# LED_Driver.net
KiCad netlist of a schematic drawn in Altium Designer
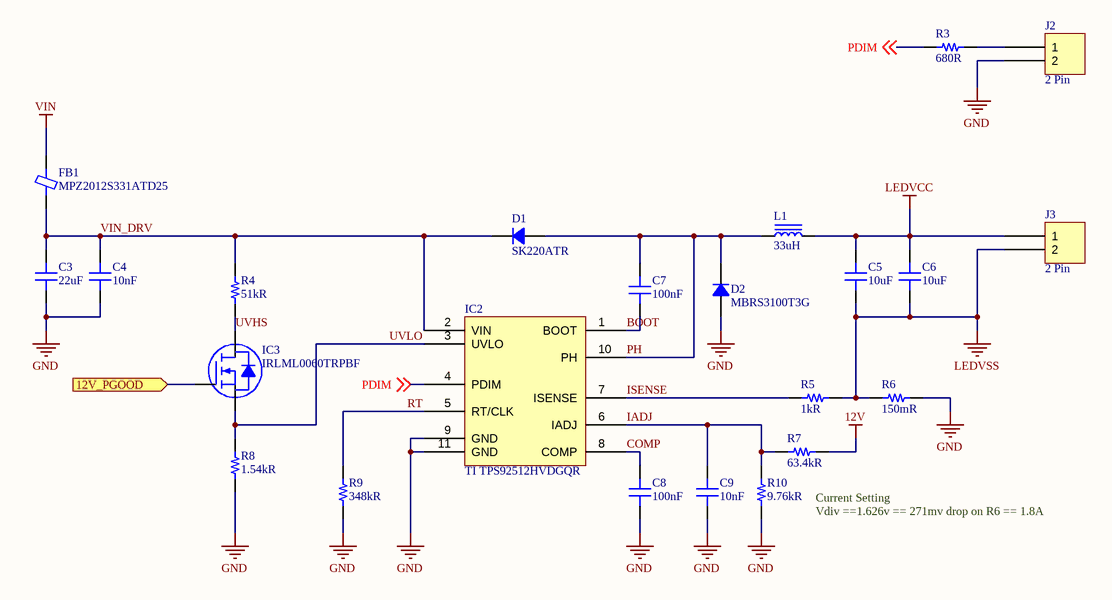
[diagram p0: LED Driver.SchDoc]

(export (version "E")
  (design (tool "Eeschema 10.0.6"))
  (components
    (comp (ref "C3")
      (value "22uF")
      (footprint "TDK CKG57N")
      (description "TDK - CKG57NX7S2A226M500JH - CAP, 22µF, 100V, 20%, X7S, 2220")
      (fields (field (name "TOLERANCE") "20%") (field (name "VOLTAGE") "100V"))
      (libsource (lib "SCH - PASSIVES - CAPACITOR") (part "Capacitor"))
    )
    (comp (ref "C4")
      (value "10nF")
      (footprint "CAP 0603/1608")
      (description "Multilayer Ceramic Capacitors MLCC - SMD/SMT .01uF 100Volts 10%")
      (fields (field (name "TOLERANCE") "10%") (field (name "VOLTAGE") "100V"))
      (libsource (lib "SCH - PASSIVES - CAPACITOR") (part "Capacitor"))
    )
    (comp (ref "C5")
      (value "10uF")
      (footprint "CAP 1210/3225 - 2.8MM")
      (description "CAP CER 10UF 50V X7R 1210")
      (fields (field (name "TOLERANCE") "10%"))
      (libsource (lib "SCH - PASSIVES - CAPACITOR") (part "Capacitor"))
    )
    (comp (ref "C6")
      (value "10uF")
      (footprint "CAP 1210/3225 - 2.8MM")
      (description "CAP CER 10UF 50V X7R 1210")
      (fields (field (name "TOLERANCE") "10%"))
      (libsource (lib "SCH - PASSIVES - CAPACITOR") (part "Capacitor"))
    )
    (comp (ref "C7")
      (value "100nF")
      (footprint "CAP 0805/2012")
      (description "Multilayer Ceramic Capacitors MLCC - SMD/SMT 50volts 0.1uF X7R 20%")
      (fields (field (name "TOLERANCE") "20%"))
      (libsource (lib "SCH - PASSIVES - CAPACITOR") (part "Capacitor"))
    )
    (comp (ref "C8")
      (value "100nF")
      (footprint "CAP 0402/1005")
      (description "MURATA - GRM155R62A104KE14D - CAP, 0.1µF, 100V, 10%, X5R, 0402")
      (fields (field (name "TOLERANCE") "10%"))
      (libsource (lib "SCH - PASSIVES - CAPACITOR") (part "Capacitor"))
    )
    (comp (ref "C9")
      (value "10nF")
      (footprint "CAP 0402/1005")
      (description "TAIYO YUDEN - TMK105B7103KV-F - CERAMIC CAPACITOR 0.01UF, 25V, X7R, 10%, 0402, FULL REEL")
      (fields (field (name "TOLERANCE") "10%") (field (name "VOLTAGE") "25V"))
      (libsource (lib "SCH - PASSIVES - CAPACITOR") (part "Capacitor"))
    )
    (comp (ref "D1")
      (value "SK220ATR")
      (footprint "ST DO214AC SMA")
      (description "DIODE SCHOTTKY 200V 2A SMA")
      (libsource (lib "SCH - DIODES - DIODE") (part "Diode"))
    )
    (comp (ref "D2")
      (value "MBRS3100T3G")
      (footprint "ST DO214AB SMC")
      (description "DIODE SCHOTTKY 100V 3A SMC")
      (libsource (lib "SCH - DIODES - DIODE") (part "Diode"))
    )
    (comp (ref "FB1")
      (value "MPZ2012S331ATD25")
      (footprint "FER 0805/2012")
      (description "Ferrite Beads 0805 330ohms 2500mA Power Line AEC-Q200")
      (fields (field (name "TOLERANCE") "25%"))
      (libsource (lib "SCH - PASSIVES - FERRITE CHIP") (part "Ferrite Chip"))
    )
    (comp (ref "IC2")
      (value "TI TPS92512HVDGQR")
      (footprint "TI MSOP-10 DGQ")
      (description "IC LED CNV CONST CUR 2.5A 10MSOP")
      (libsource (lib "SCH - DRIVER - LED - TI TPS92512HVDGQR") (part "TI TPS92512HVDGQR"))
    )
    (comp (ref "IC3")
      (value "IRLML0060TRPBF")
      (footprint "INFINEON SOT-23-3")
      (description "MOSFET MOSFT 60V 2.7A 92mOhm 2.5nC Qg")
      (libsource (lib "SCH - FET - N-CH - INFINEON MOSFET N-CH SOT-23-3 GSD") (part "INFINEON MOSFET N-CH SOT-23-3 GSD"))
    )
    (comp (ref "J2")
      (value "2 Pin")
      (footprint "TE 282834-2")
      (description "TERM BLK 2P SIDE ENT 2.54MM PCB")
      (fields (field (name "VOLTAGE") "150V"))
      (libsource (lib "SCH - CONNECTORS - 2 PIN") (part "2 Pin"))
    )
    (comp (ref "J3")
      (value "2 Pin")
      (footprint "FCI 06-381-2PIN")
      (description "TERM BLOCK HDR 2POS 90DEG 3.81MM")
      (libsource (lib "SCH - CONNECTORS - 2 PIN") (part "2 Pin"))
    )
    (comp (ref "L1")
      (value "33uH")
      (footprint "TDK SLF12575")
      (description "INDUCTOR SHIELD PWR 33UH 12575")
      (fields (field (name "TOLERANCE") "20%"))
      (libsource (lib "SCH - PASSIVES - INDUCTOR") (part "Inductor"))
    )
    (comp (ref "R3")
      (value "680R")
      (footprint "RES 0402/1005")
      (description "ESR Series 680 Ω ±5 % 0.33 W ±200 ppm/°C 1206 SMT Anti-Surge Chip Resistor")
      (fields (field (name "TOLERANCE") "5%"))
      (libsource (lib "SCH - PASSIVES - RESISTOR") (part "Resistor"))
    )
    (comp (ref "R4")
      (value "51kR")
      (footprint "RES 0402/1005")
      (description "RES SMD 51K OHM 5% 1/16W 0402")
      (fields (field (name "TOLERANCE") "5%"))
      (libsource (lib "SCH - PASSIVES - RESISTOR") (part "Resistor"))
    )
    (comp (ref "R5")
      (value "1kR")
      (footprint "RES 0402/1005")
      (description "RES SMD 1K OHM 1% 1/16W 0402")
      (fields (field (name "TOLERANCE") "1%"))
      (libsource (lib "SCH - PASSIVES - RESISTOR") (part "Resistor"))
    )
    (comp (ref "R6")
      (value "150mR")
      (footprint "STACKPOLE CSRN2512")
      (description "RES 0.15 OHM 1% 2W 2512")
      (fields (field (name "TOLERANCE") "1%"))
      (libsource (lib "SCH - PASSIVES - RESISTOR") (part "Resistor"))
    )
    (comp (ref "R7")
      (value "63.4kR")
      (footprint "RES 0402/1005")
      (description "Thick Film Resistors - SMD 63.4K OHM 1%")
      (fields (field (name "TOLERANCE") "1%"))
      (libsource (lib "SCH - PASSIVES - RESISTOR") (part "Resistor"))
    )
    (comp (ref "R8")
      (value "1.54kR")
      (footprint "RES 0402/1005")
      (description "RES SMD 1.54K OHM 1% 1/16W 0402")
      (fields (field (name "TOLERANCE") "1%"))
      (libsource (lib "SCH - PASSIVES - RESISTOR") (part "Resistor"))
    )
    (comp (ref "R9")
      (value "348kR")
      (footprint "RES 0402/1005")
      (description "Res Thick Film 0402 348K Ohm 1% 1/16W ±100ppm/°C Molded SMD Paper T/R")
      (fields (field (name "TOLERANCE") "1%"))
      (libsource (lib "SCH - PASSIVES - RESISTOR") (part "Resistor"))
    )
    (comp (ref "R10")
      (value "9.76kR")
      (footprint "RES 0402/1005")
      (description "Thick Film Resistors - SMD 9.76K OHM 1%")
      (fields (field (name "TOLERANCE") "1%"))
      (libsource (lib "SCH - PASSIVES - RESISTOR") (part "Resistor"))
    )
  )
  (nets
    (net (code "1") (name "/12V_PGOOD") (class "Default")
      (node (ref "IC3") (pin "1") (pinfunction "G_1") (pintype "passive"))
    )
    (net (code "2") (name "/BOOT") (class "Default")
      (node (ref "C7") (pin "2") (pinfunction "2_2") (pintype "passive"))
      (node (ref "IC2") (pin "1") (pinfunction "BOOT_1") (pintype "passive"))
    )
    (net (code "3") (name "/COMP") (class "Default")
      (node (ref "C8") (pin "1") (pinfunction "1_1") (pintype "passive"))
      (node (ref "IC2") (pin "8") (pinfunction "COMP_8") (pintype "passive"))
    )
    (net (code "4") (name "/IADJ") (class "Default")
      (node (ref "C9") (pin "2") (pinfunction "2_2") (pintype "passive"))
      (node (ref "IC2") (pin "6") (pinfunction "IADJ_6") (pintype "passive"))
      (node (ref "R10") (pin "2") (pinfunction "2_2") (pintype "passive"))
      (node (ref "R7") (pin "2") (pinfunction "2_2") (pintype "passive"))
    )
    (net (code "5") (name "/ISENSE") (class "Default")
      (node (ref "IC2") (pin "7") (pinfunction "ISENSE_7") (pintype "passive"))
      (node (ref "R5") (pin "1") (pinfunction "1_1") (pintype "passive"))
    )
    (net (code "6") (name "/PH") (class "Default")
      (node (ref "C7") (pin "1") (pinfunction "1_1") (pintype "passive"))
      (node (ref "D1") (pin "1") (pinfunction "1_1") (pintype "passive"))
      (node (ref "D2") (pin "2") (pinfunction "2_2") (pintype "passive"))
      (node (ref "IC2") (pin "10") (pinfunction "PH_10") (pintype "passive"))
      (node (ref "L1") (pin "1") (pinfunction "1_1") (pintype "passive"))
    )
    (net (code "7") (name "/RT") (class "Default")
      (node (ref "IC2") (pin "5") (pinfunction "RT/CLK_5") (pintype "passive"))
      (node (ref "R9") (pin "2") (pinfunction "2_2") (pintype "passive"))
    )
    (net (code "8") (name "/UVHS") (class "Default")
      (node (ref "IC3") (pin "3") (pinfunction "D_3") (pintype "passive"))
      (node (ref "R4") (pin "1") (pinfunction "1_1") (pintype "passive"))
    )
    (net (code "9") (name "/UVLO") (class "Default")
      (node (ref "IC2") (pin "3") (pinfunction "UVLO_3") (pintype "passive"))
      (node (ref "IC3") (pin "2") (pinfunction "S_2") (pintype "passive"))
      (node (ref "R8") (pin "2") (pinfunction "2_2") (pintype "passive"))
    )
    (net (code "10") (name "/VIN_DRV") (class "Default")
      (node (ref "C3") (pin "2") (pinfunction "2_2") (pintype "passive"))
      (node (ref "C4") (pin "2") (pinfunction "2_2") (pintype "passive"))
      (node (ref "D1") (pin "2") (pinfunction "2_2") (pintype "passive"))
      (node (ref "FB1") (pin "1") (pinfunction "1_1") (pintype "passive"))
      (node (ref "IC2") (pin "2") (pinfunction "VIN_2") (pintype "passive"))
      (node (ref "R4") (pin "2") (pinfunction "2_2") (pintype "passive"))
    )
    (net (code "11") (name "12V") (class "Default")
      (node (ref "R7") (pin "1") (pinfunction "1_1") (pintype "passive"))
    )
    (net (code "12") (name "GND") (class "Default")
      (node (ref "C3") (pin "1") (pinfunction "1_1") (pintype "passive"))
      (node (ref "C4") (pin "1") (pinfunction "1_1") (pintype "passive"))
      (node (ref "C8") (pin "2") (pinfunction "2_2") (pintype "passive"))
      (node (ref "C9") (pin "1") (pinfunction "1_1") (pintype "passive"))
      (node (ref "D2") (pin "1") (pinfunction "1_1") (pintype "passive"))
      (node (ref "IC2") (pin "11") (pinfunction "GND_11") (pintype "passive"))
      (node (ref "IC2") (pin "9") (pinfunction "GND_9") (pintype "passive"))
      (node (ref "J2") (pin "2") (pinfunction "2_2") (pintype "passive"))
      (node (ref "R10") (pin "1") (pinfunction "1_1") (pintype "passive"))
      (node (ref "R6") (pin "1") (pinfunction "1_1") (pintype "passive"))
      (node (ref "R8") (pin "1") (pinfunction "1_1") (pintype "passive"))
      (node (ref "R9") (pin "1") (pinfunction "1_1") (pintype "passive"))
    )
    (net (code "13") (name "LEDVCC") (class "Default")
      (node (ref "C5") (pin "2") (pinfunction "2_2") (pintype "passive"))
      (node (ref "C6") (pin "2") (pinfunction "2_2") (pintype "passive"))
      (node (ref "J3") (pin "1") (pinfunction "1_1") (pintype "passive"))
      (node (ref "L1") (pin "2") (pinfunction "2_2") (pintype "passive"))
    )
    (net (code "14") (name "LEDVSS") (class "Default")
      (node (ref "C5") (pin "1") (pinfunction "1_1") (pintype "passive"))
      (node (ref "C6") (pin "1") (pinfunction "1_1") (pintype "passive"))
      (node (ref "J3") (pin "2") (pinfunction "2_2") (pintype "passive"))
      (node (ref "R5") (pin "2") (pinfunction "2_2") (pintype "passive"))
      (node (ref "R6") (pin "2") (pinfunction "2_2") (pintype "passive"))
    )
    (net (code "15") (name "Net-(J2-Pad1)") (class "Default")
      (node (ref "J2") (pin "1") (pinfunction "1_1") (pintype "passive"))
      (node (ref "R3") (pin "2") (pinfunction "2_2") (pintype "passive"))
    )
    (net (code "16") (name "PDIM") (class "Default")
      (node (ref "IC2") (pin "4") (pinfunction "PDIM_4") (pintype "passive"))
      (node (ref "R3") (pin "1") (pinfunction "1_1") (pintype "passive"))
    )
    (net (code "17") (name "VIN") (class "Default")
      (node (ref "FB1") (pin "2") (pinfunction "2_2") (pintype "passive"))
    )
  )
)
